# Sensors.net
KiCad netlist of a schematic drawn in Altium Designer
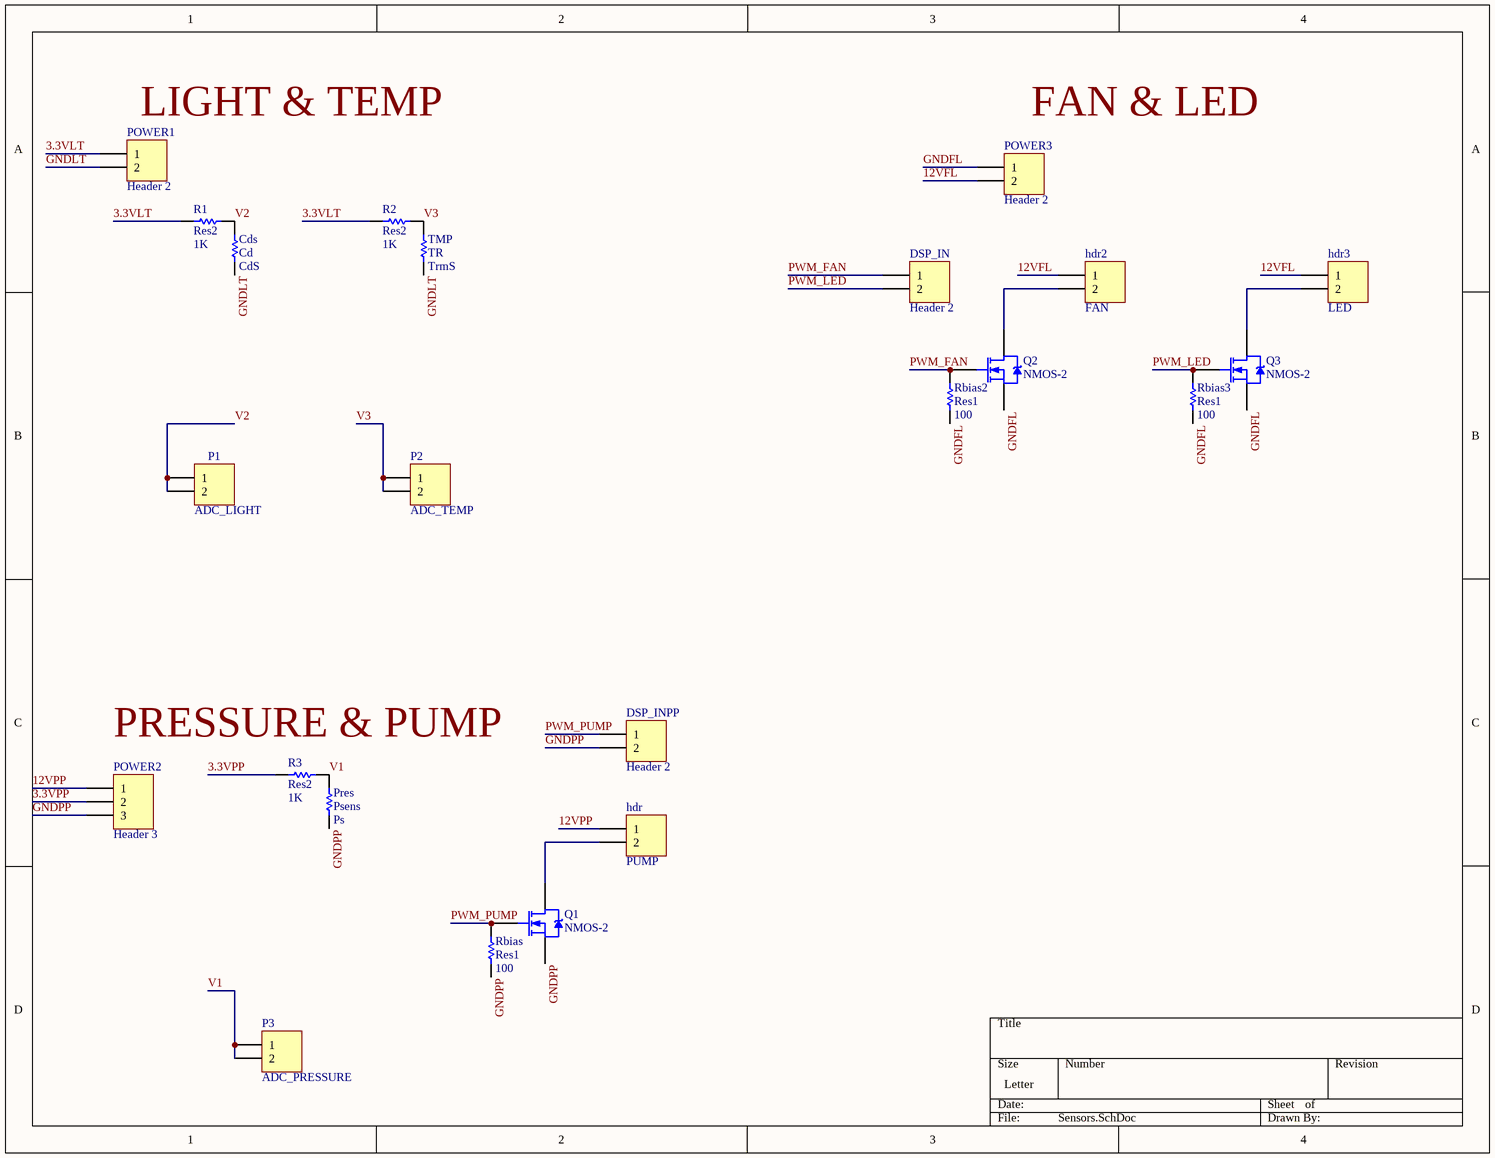
[diagram p0: Sensors.SchDoc]

(export (version "E")
  (design (tool "Eeschema 10.0.6"))
  (components
    (comp (ref "Cds")
      (value "Cd")
      (footprint "AXIAL-0.3")
      (description "Resistor")
      (fields (field (name "ALTIUM_VALUE") "CdS") (field (name "PUBLISHER") "Altium Limited"))
      (libsource (lib "Miscellaneous Devices") (part "Res1"))
    )
    (comp (ref "DSP_IN")
      (value "Header 2")
      (footprint "HDR1X2")
      (description "Header, 2-Pin")
      (fields (field (name "PUBLISHER") "Altium Limited"))
      (libsource (lib "Miscellaneous Connectors") (part "Header 2"))
    )
    (comp (ref "DSP_INPP")
      (value "Header 2")
      (footprint "HDR1X2")
      (description "Header, 2-Pin")
      (fields (field (name "PUBLISHER") "Altium Limited"))
      (libsource (lib "Miscellaneous Connectors") (part "Header 2"))
    )
    (comp (ref "hdr")
      (value "PUMP")
      (footprint "HDR1X2")
      (description "Header, 2-Pin")
      (fields (field (name "PUBLISHER") "Altium Limited"))
      (libsource (lib "Miscellaneous Connectors") (part "Header 2"))
    )
    (comp (ref "hdr2")
      (value "FAN")
      (footprint "HDR1X2")
      (description "Header, 2-Pin")
      (fields (field (name "PUBLISHER") "Altium Limited"))
      (libsource (lib "Miscellaneous Connectors") (part "Header 2"))
    )
    (comp (ref "hdr3")
      (value "LED")
      (footprint "HDR1X2")
      (description "Header, 2-Pin")
      (fields (field (name "PUBLISHER") "Altium Limited"))
      (libsource (lib "Miscellaneous Connectors") (part "Header 2"))
    )
    (comp (ref "P1")
      (value "ADC_LIGHT")
      (footprint "HDR1X2")
      (description "Header, 2-Pin")
      (fields (field (name "PUBLISHER") "Altium Limited"))
      (libsource (lib "Miscellaneous Connectors") (part "Header 2"))
    )
    (comp (ref "P2")
      (value "ADC_TEMP")
      (footprint "HDR1X2")
      (description "Header, 2-Pin")
      (fields (field (name "PUBLISHER") "Altium Limited"))
      (libsource (lib "Miscellaneous Connectors") (part "Header 2"))
    )
    (comp (ref "P3")
      (value "ADC_PRESSURE")
      (footprint "HDR1X2")
      (description "Header, 2-Pin")
      (fields (field (name "PUBLISHER") "Altium Limited"))
      (libsource (lib "Miscellaneous Connectors") (part "Header 2"))
    )
    (comp (ref "POWER1")
      (value "Header 2")
      (footprint "HDR1X2")
      (description "Header, 2-Pin")
      (fields (field (name "PUBLISHER") "Altium Limited"))
      (libsource (lib "Miscellaneous Connectors") (part "Header 2"))
    )
    (comp (ref "POWER2")
      (value "Header 3")
      (footprint "HDR1X3")
      (description "Header, 3-Pin")
      (fields (field (name "PUBLISHER") "Altium Limited"))
      (libsource (lib "Miscellaneous Connectors") (part "Header 3"))
    )
    (comp (ref "POWER3")
      (value "Header 2")
      (footprint "HDR1X2")
      (description "Header, 2-Pin")
      (fields (field (name "PUBLISHER") "Altium Limited"))
      (libsource (lib "Miscellaneous Connectors") (part "Header 2"))
    )
    (comp (ref "Pres")
      (value "Psens")
      (footprint "AXIAL-0.3")
      (description "Resistor")
      (fields (field (name "ALTIUM_VALUE") "Ps") (field (name "PUBLISHER") "Altium Limited"))
      (libsource (lib "Miscellaneous Devices") (part "Res1"))
    )
    (comp (ref "Q1")
      (value "NMOS-2")
      (footprint "TO-220AB")
      (description "N-Channel Power MOSFET")
      (fields (field (name "PUBLISHER") "Altium Limited"))
      (libsource (lib "Miscellaneous Devices") (part "NMOS-2"))
    )
    (comp (ref "Q2")
      (value "NMOS-2")
      (footprint "TO-220AB")
      (description "N-Channel Power MOSFET")
      (fields (field (name "PUBLISHER") "Altium Limited"))
      (libsource (lib "Miscellaneous Devices") (part "NMOS-2"))
    )
    (comp (ref "Q3")
      (value "NMOS-2")
      (footprint "TO-220AB")
      (description "N-Channel Power MOSFET")
      (fields (field (name "PUBLISHER") "Altium Limited"))
      (libsource (lib "Miscellaneous Devices") (part "NMOS-2"))
    )
    (comp (ref "R1")
      (value "Res2")
      (footprint "AXIAL-0.3")
      (description "Resistor")
      (fields (field (name "ALTIUM_VALUE") "1K") (field (name "PUBLISHER") "Altium Limited"))
      (libsource (lib "Miscellaneous Devices") (part "Res1"))
    )
    (comp (ref "R2")
      (value "Res2")
      (footprint "AXIAL-0.3")
      (description "Resistor")
      (fields (field (name "ALTIUM_VALUE") "1K") (field (name "PUBLISHER") "Altium Limited"))
      (libsource (lib "Miscellaneous Devices") (part "Res1"))
    )
    (comp (ref "R3")
      (value "Res2")
      (footprint "AXIAL-0.3")
      (description "Resistor")
      (fields (field (name "ALTIUM_VALUE") "1K") (field (name "PUBLISHER") "Altium Limited"))
      (libsource (lib "Miscellaneous Devices") (part "Res1"))
    )
    (comp (ref "Rbias")
      (value "Res1")
      (footprint "AXIAL-0.3")
      (description "Resistor")
      (fields (field (name "ALTIUM_VALUE") "100") (field (name "PUBLISHER") "Altium Limited"))
      (libsource (lib "Miscellaneous Devices") (part "Res1"))
    )
    (comp (ref "Rbias2")
      (value "Res1")
      (footprint "AXIAL-0.3")
      (description "Resistor")
      (fields (field (name "ALTIUM_VALUE") "100") (field (name "PUBLISHER") "Altium Limited"))
      (libsource (lib "Miscellaneous Devices") (part "Res1"))
    )
    (comp (ref "Rbias3")
      (value "Res1")
      (footprint "AXIAL-0.3")
      (description "Resistor")
      (fields (field (name "ALTIUM_VALUE") "100") (field (name "PUBLISHER") "Altium Limited"))
      (libsource (lib "Miscellaneous Devices") (part "Res1"))
    )
    (comp (ref "TMP")
      (value "TR")
      (footprint "AXIAL-0.3")
      (description "Resistor")
      (fields (field (name "ALTIUM_VALUE") "TrmS") (field (name "PUBLISHER") "Altium Limited"))
      (libsource (lib "Miscellaneous Devices") (part "Res1"))
    )
  )
  (nets
    (net (code "1") (name "/3.3VLT") (class "Default")
      (node (ref "POWER1") (pin "1") (pinfunction "1_1") (pintype "passive"))
      (node (ref "R1") (pin "2") (pinfunction "2_2") (pintype "passive"))
      (node (ref "R2") (pin "2") (pinfunction "2_2") (pintype "passive"))
    )
    (net (code "2") (name "/3.3VPP") (class "Default")
      (node (ref "POWER2") (pin "2") (pinfunction "2_2") (pintype "passive"))
      (node (ref "R3") (pin "2") (pinfunction "2_2") (pintype "passive"))
    )
    (net (code "3") (name "/12VFL") (class "Default")
      (node (ref "POWER3") (pin "2") (pinfunction "2_2") (pintype "passive"))
      (node (ref "hdr2") (pin "1") (pinfunction "1_1") (pintype "passive"))
      (node (ref "hdr3") (pin "1") (pinfunction "1_1") (pintype "passive"))
    )
    (net (code "4") (name "/12VPP") (class "Default")
      (node (ref "POWER2") (pin "1") (pinfunction "1_1") (pintype "passive"))
      (node (ref "hdr") (pin "1") (pinfunction "1_1") (pintype "passive"))
    )
    (net (code "6") (name "/GNDFL") (class "Default")
      (node (ref "POWER3") (pin "1") (pinfunction "1_1") (pintype "passive"))
      (node (ref "Q2") (pin "3") (pinfunction "S_3") (pintype "passive"))
      (node (ref "Q3") (pin "3") (pinfunction "S_3") (pintype "passive"))
      (node (ref "Rbias2") (pin "1") (pinfunction "1_1") (pintype "passive"))
      (node (ref "Rbias3") (pin "1") (pinfunction "1_1") (pintype "passive"))
    )
    (net (code "7") (name "/GNDLT") (class "Default")
      (node (ref "Cds") (pin "1") (pinfunction "1_1") (pintype "passive"))
      (node (ref "POWER1") (pin "2") (pinfunction "2_2") (pintype "passive"))
      (node (ref "TMP") (pin "1") (pinfunction "1_1") (pintype "passive"))
    )
    (net (code "8") (name "/GNDPP") (class "Default")
      (node (ref "DSP_INPP") (pin "2") (pinfunction "2_2") (pintype "passive"))
      (node (ref "POWER2") (pin "3") (pinfunction "3_3") (pintype "passive"))
      (node (ref "Pres") (pin "1") (pinfunction "1_1") (pintype "passive"))
      (node (ref "Q1") (pin "3") (pinfunction "S_3") (pintype "passive"))
      (node (ref "Rbias") (pin "1") (pinfunction "1_1") (pintype "passive"))
    )
    (net (code "11") (name "/PWM_FAN") (class "Default")
      (node (ref "DSP_IN") (pin "1") (pinfunction "1_1") (pintype "passive"))
      (node (ref "Q2") (pin "1") (pinfunction "G_1") (pintype "passive"))
      (node (ref "Rbias2") (pin "2") (pinfunction "2_2") (pintype "passive"))
    )
    (net (code "12") (name "/PWM_LED") (class "Default")
      (node (ref "DSP_IN") (pin "2") (pinfunction "2_2") (pintype "passive"))
      (node (ref "Q3") (pin "1") (pinfunction "G_1") (pintype "passive"))
      (node (ref "Rbias3") (pin "2") (pinfunction "2_2") (pintype "passive"))
    )
    (net (code "13") (name "/PWM_PUMP") (class "Default")
      (node (ref "DSP_INPP") (pin "1") (pinfunction "1_1") (pintype "passive"))
      (node (ref "Q1") (pin "1") (pinfunction "G_1") (pintype "passive"))
      (node (ref "Rbias") (pin "2") (pinfunction "2_2") (pintype "passive"))
    )
    (net (code "14") (name "/V1") (class "Default")
      (node (ref "P3") (pin "1") (pinfunction "1_1") (pintype "passive"))
      (node (ref "P3") (pin "2") (pinfunction "2_2") (pintype "passive"))
      (node (ref "Pres") (pin "2") (pinfunction "2_2") (pintype "passive"))
      (node (ref "R3") (pin "1") (pinfunction "1_1") (pintype "passive"))
    )
    (net (code "15") (name "/V2") (class "Default")
      (node (ref "Cds") (pin "2") (pinfunction "2_2") (pintype "passive"))
      (node (ref "P1") (pin "1") (pinfunction "1_1") (pintype "passive"))
      (node (ref "P1") (pin "2") (pinfunction "2_2") (pintype "passive"))
      (node (ref "R1") (pin "1") (pinfunction "1_1") (pintype "passive"))
    )
    (net (code "16") (name "/V3") (class "Default")
      (node (ref "P2") (pin "1") (pinfunction "1_1") (pintype "passive"))
      (node (ref "P2") (pin "2") (pinfunction "2_2") (pintype "passive"))
      (node (ref "R2") (pin "1") (pinfunction "1_1") (pintype "passive"))
      (node (ref "TMP") (pin "2") (pinfunction "2_2") (pintype "passive"))
    )
    (net (code "17") (name "Net-(Q1-D)") (class "Default")
      (node (ref "Q1") (pin "2") (pinfunction "D_2") (pintype "passive"))
      (node (ref "hdr") (pin "2") (pinfunction "2_2") (pintype "passive"))
    )
    (net (code "18") (name "Net-(Q2-D)") (class "Default")
      (node (ref "Q2") (pin "2") (pinfunction "D_2") (pintype "passive"))
      (node (ref "hdr2") (pin "2") (pinfunction "2_2") (pintype "passive"))
    )
    (net (code "19") (name "Net-(Q3-D)") (class "Default")
      (node (ref "Q3") (pin "2") (pinfunction "D_2") (pintype "passive"))
      (node (ref "hdr3") (pin "2") (pinfunction "2_2") (pintype "passive"))
    )
  )
)
